# 3tastsp_v4_resistorcooldrive_battcheck.net
KiCad netlist of a schematic drawn in EAGLE
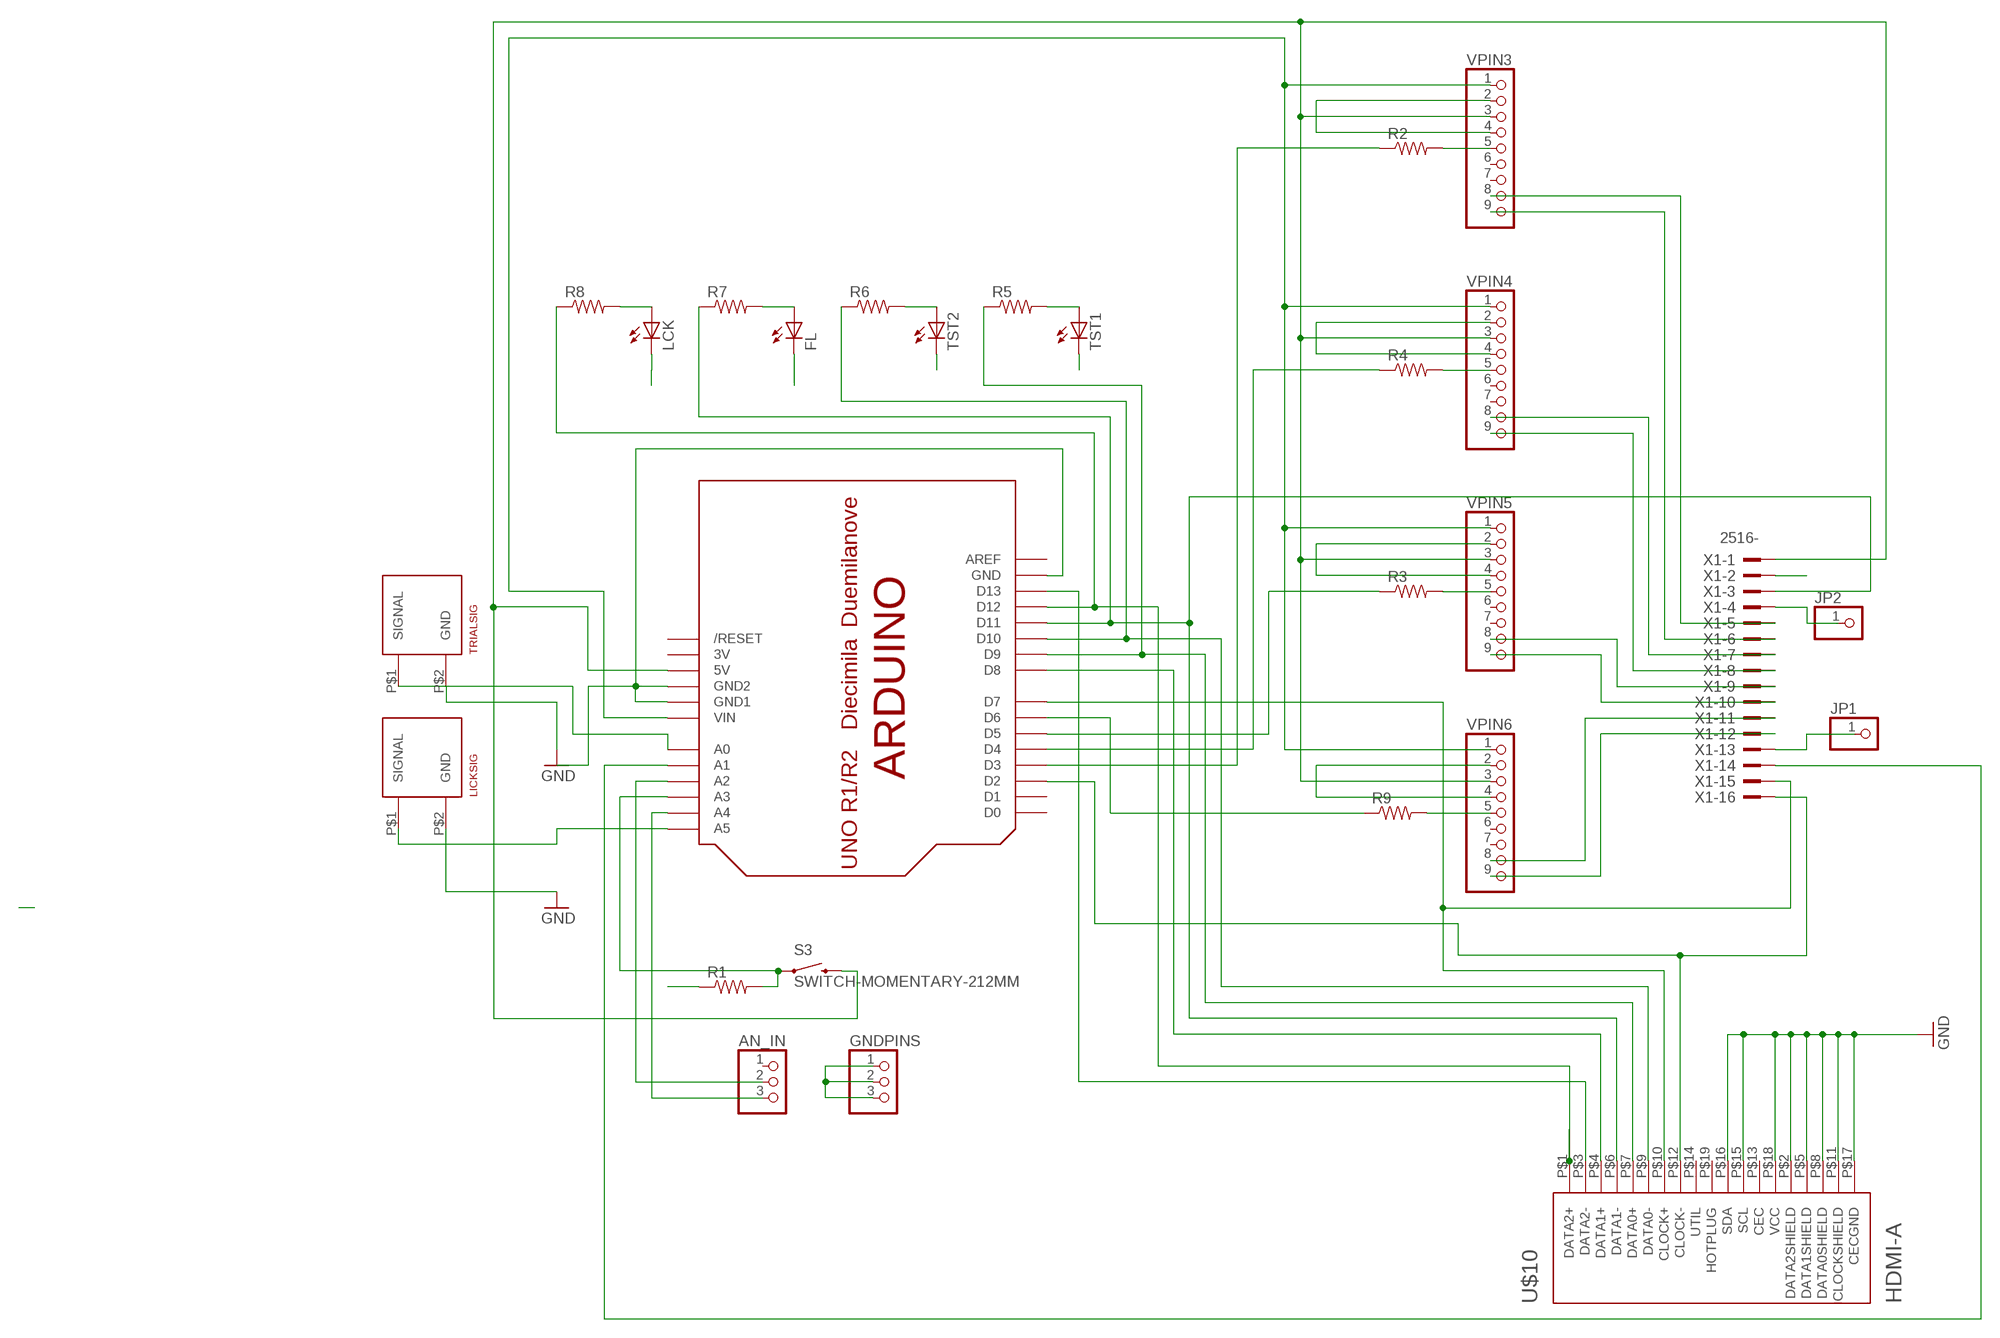
[diagram p0: schematic, sheet 1]

(export (version "E")
  (design (tool "Eeschema 10.0.6"))
  (components
    (comp (ref "AN_IN")
      (value "PINHD-1X3")
      (footprint "eagle-import:1X03")
      (libsource (lib "eagle-import") (part "PINHD-1X3"))
    )
    (comp (ref "FL")
      (value "LED5MM")
      (footprint "eagle-import:LED5MM")
      (libsource (lib "eagle-import") (part "LED5MM"))
    )
    (comp (ref "GNDPINS")
      (value "PINHD-1X3")
      (footprint "eagle-import:1X03")
      (libsource (lib "eagle-import") (part "PINHD-1X3"))
    )
    (comp (ref "JP1")
      (value "PINHD-1X1")
      (footprint "eagle-import:1X01")
      (libsource (lib "eagle-import") (part "PINHD-1X1"))
    )
    (comp (ref "JP2")
      (value "PINHD-1X1")
      (footprint "eagle-import:1X01")
      (libsource (lib "eagle-import") (part "PINHD-1X1"))
    )
    (comp (ref "LCK")
      (value "LED5MM")
      (footprint "eagle-import:LED5MM")
      (libsource (lib "eagle-import") (part "LED5MM"))
    )
    (comp (ref "LICKSIG")
      (value "BNC_VERTICAL")
      (footprint "eagle-import:BNC_VERTICAL")
      (libsource (lib "eagle-import") (part "BNC_VERTICAL"))
    )
    (comp (ref "R1")
      (value "RESISTORPTH-1/2W")
      (footprint "eagle-import:AXIAL-0.5")
      (libsource (lib "eagle-import") (part "RESISTORPTH-1/2W"))
    )
    (comp (ref "R2")
      (value "RESISTORPTH-1/2W")
      (footprint "eagle-import:AXIAL-0.5")
      (libsource (lib "eagle-import") (part "RESISTORPTH-1/2W"))
    )
    (comp (ref "R3")
      (value "RESISTORPTH-1/2W")
      (footprint "eagle-import:AXIAL-0.5")
      (libsource (lib "eagle-import") (part "RESISTORPTH-1/2W"))
    )
    (comp (ref "R4")
      (value "RESISTORPTH-1/2W")
      (footprint "eagle-import:AXIAL-0.5")
      (libsource (lib "eagle-import") (part "RESISTORPTH-1/2W"))
    )
    (comp (ref "R5")
      (value "RESISTORPTH-1/2W")
      (footprint "eagle-import:AXIAL-0.5")
      (libsource (lib "eagle-import") (part "RESISTORPTH-1/2W"))
    )
    (comp (ref "R6")
      (value "RESISTORPTH-1/2W")
      (footprint "eagle-import:AXIAL-0.5")
      (libsource (lib "eagle-import") (part "RESISTORPTH-1/2W"))
    )
    (comp (ref "R7")
      (value "RESISTORPTH-1/2W")
      (footprint "eagle-import:AXIAL-0.5")
      (libsource (lib "eagle-import") (part "RESISTORPTH-1/2W"))
    )
    (comp (ref "R8")
      (value "RESISTORPTH-1/2W")
      (footprint "eagle-import:AXIAL-0.5")
      (libsource (lib "eagle-import") (part "RESISTORPTH-1/2W"))
    )
    (comp (ref "R9")
      (value "RESISTORPTH-1/2W")
      (footprint "eagle-import:AXIAL-0.5")
      (libsource (lib "eagle-import") (part "RESISTORPTH-1/2W"))
    )
    (comp (ref "S3")
      (value "SWITCH-MOMENTARY-212MM")
      (footprint "eagle-import:TACTILE-PTH-12MM")
      (libsource (lib "eagle-import") (part "SWITCH-MOMENTARY-212MM"))
    )
    (comp (ref "TRIALSIG")
      (value "BNC_VERTICAL")
      (footprint "eagle-import:BNC_VERTICAL")
      (libsource (lib "eagle-import") (part "BNC_VERTICAL"))
    )
    (comp (ref "TST1")
      (value "LED5MM")
      (footprint "eagle-import:LED5MM")
      (libsource (lib "eagle-import") (part "LED5MM"))
    )
    (comp (ref "TST2")
      (value "LED5MM")
      (footprint "eagle-import:LED5MM")
      (libsource (lib "eagle-import") (part "LED5MM"))
    )
    (comp (ref "U$1")
      (value "ARDUINO-NOHOLE")
      (footprint "eagle-import:ARDUINO-NOHOLE")
      (libsource (lib "eagle-import") (part "ARDUINO-NOHOLE"))
    )
    (comp (ref "U$10")
      (value "HDMI-A")
      (footprint "eagle-import:HDMI_A")
      (libsource (lib "eagle-import") (part "HDMI-A"))
    )
    (comp (ref "VPIN3")
      (value "PINHD-1X9")
      (footprint "eagle-import:1X09")
      (libsource (lib "eagle-import") (part "PINHD-1X9"))
    )
    (comp (ref "VPIN4")
      (value "PINHD-1X9")
      (footprint "eagle-import:1X09")
      (libsource (lib "eagle-import") (part "PINHD-1X9"))
    )
    (comp (ref "VPIN5")
      (value "PINHD-1X9")
      (footprint "eagle-import:1X09")
      (libsource (lib "eagle-import") (part "PINHD-1X9"))
    )
    (comp (ref "VPIN6")
      (value "PINHD-1X9")
      (footprint "eagle-import:1X09")
      (libsource (lib "eagle-import") (part "PINHD-1X9"))
    )
    (comp (ref "X1")
      (value "2516-")
      (footprint "eagle-import:PAK100_2500-16")
      (libsource (lib "eagle-import") (part "2516-"))
    )
  )
  (nets
    (net (code "1") (name "/3V") (class "Default")
      (node (ref "U$1") (pin "3V") (pinfunction "3V_3V") (pintype "power_in"))
    )
    (net (code "2") (name "GND") (class "Default")
      (node (ref "FL") (pin "K") (pinfunction "C_K") (pintype "passive"))
      (node (ref "GNDPINS") (pin "1") (pinfunction "1_1") (pintype "passive"))
      (node (ref "GNDPINS") (pin "2") (pinfunction "2_2") (pintype "passive"))
      (node (ref "GNDPINS") (pin "3") (pinfunction "3_3") (pintype "passive"))
      (node (ref "LCK") (pin "K") (pinfunction "C_K") (pintype "passive"))
      (node (ref "LICKSIG") (pin "P$2") (pinfunction "GND_P$2") (pintype "bidirectional"))
      (node (ref "R1") (pin "P$1") (pinfunction "1_P$1") (pintype "passive"))
      (node (ref "TRIALSIG") (pin "P$2") (pinfunction "GND_P$2") (pintype "bidirectional"))
      (node (ref "TST1") (pin "K") (pinfunction "C_K") (pintype "passive"))
      (node (ref "TST2") (pin "K") (pinfunction "C_K") (pintype "passive"))
      (node (ref "U$1") (pin "GND") (pinfunction "GND_GND") (pintype "power_in"))
      (node (ref "U$1") (pin "GND1") (pinfunction "GND1_GND1") (pintype "power_in"))
      (node (ref "U$1") (pin "GND2") (pinfunction "GND2_GND2") (pintype "power_in"))
      (node (ref "U$10") (pin "P$11") (pinfunction "CLOCKSHIELD_P$11") (pintype "bidirectional"))
      (node (ref "U$10") (pin "P$15") (pinfunction "SCL_P$15") (pintype "bidirectional"))
      (node (ref "U$10") (pin "P$16") (pinfunction "SDA_P$16") (pintype "bidirectional"))
      (node (ref "U$10") (pin "P$17") (pinfunction "CECGND_P$17") (pintype "bidirectional"))
      (node (ref "U$10") (pin "P$18") (pinfunction "VCC_P$18") (pintype "bidirectional"))
      (node (ref "U$10") (pin "P$2") (pinfunction "DATA2SHIELD_P$2") (pintype "bidirectional"))
      (node (ref "U$10") (pin "P$5") (pinfunction "DATA1SHIELD_P$5") (pintype "bidirectional"))
      (node (ref "U$10") (pin "P$8") (pinfunction "DATA0SHIELD_P$8") (pintype "bidirectional"))
      (node (ref "VPIN3") (pin "2") (pinfunction "2_2") (pintype "passive"))
      (node (ref "VPIN3") (pin "4") (pinfunction "4_4") (pintype "passive"))
      (node (ref "VPIN4") (pin "2") (pinfunction "2_2") (pintype "passive"))
      (node (ref "VPIN4") (pin "4") (pinfunction "4_4") (pintype "passive"))
      (node (ref "VPIN5") (pin "2") (pinfunction "2_2") (pintype "passive"))
      (node (ref "VPIN5") (pin "4") (pinfunction "4_4") (pintype "passive"))
      (node (ref "VPIN6") (pin "2") (pinfunction "2_2") (pintype "passive"))
      (node (ref "VPIN6") (pin "4") (pinfunction "4_4") (pintype "passive"))
      (node (ref "X1") (pin "2") (pinfunction "KL_2") (pintype "passive"))
    )
    (net (code "3") (name "Net-(AN_IN-Pad2)") (class "Default")
      (node (ref "AN_IN") (pin "2") (pinfunction "2_2") (pintype "passive"))
      (node (ref "U$1") (pin "A2") (pinfunction "A2_A2") (pintype "bidirectional"))
    )
    (net (code "4") (name "Net-(AN_IN-Pad3)") (class "Default")
      (node (ref "AN_IN") (pin "3") (pinfunction "3_3") (pintype "passive"))
      (node (ref "U$1") (pin "A4") (pinfunction "A4_A4") (pintype "bidirectional"))
    )
    (net (code "5") (name "Net-(LICKSIG-SIGNAL)") (class "Default")
      (node (ref "LICKSIG") (pin "P$1") (pinfunction "SIGNAL_P$1") (pintype "bidirectional"))
      (node (ref "U$1") (pin "A5") (pinfunction "A5_A5") (pintype "bidirectional"))
    )
    (net (code "6") (name "Net-(R1-2)") (class "Default")
      (node (ref "R1") (pin "P$2") (pinfunction "2_P$2") (pintype "passive"))
      (node (ref "S3") (pin "1") (pinfunction "1_1") (pintype "passive"))
      (node (ref "U$1") (pin "A3") (pinfunction "A3_A3") (pintype "bidirectional"))
    )
    (net (code "7") (name "Net-(R2-1)") (class "Default")
      (node (ref "R2") (pin "P$1") (pinfunction "1_P$1") (pintype "passive"))
      (node (ref "U$1") (pin "D3") (pinfunction "D3_D3") (pintype "bidirectional"))
    )
    (net (code "8") (name "Net-(R2-2)") (class "Default")
      (node (ref "R2") (pin "P$2") (pinfunction "2_P$2") (pintype "passive"))
      (node (ref "VPIN3") (pin "5") (pinfunction "5_5") (pintype "passive"))
    )
    (net (code "9") (name "Net-(R3-1)") (class "Default")
      (node (ref "R3") (pin "P$1") (pinfunction "1_P$1") (pintype "passive"))
      (node (ref "U$1") (pin "D5") (pinfunction "D5_D5") (pintype "bidirectional"))
    )
    (net (code "10") (name "Net-(R3-2)") (class "Default")
      (node (ref "R3") (pin "P$2") (pinfunction "2_P$2") (pintype "passive"))
      (node (ref "VPIN5") (pin "5") (pinfunction "5_5") (pintype "passive"))
    )
    (net (code "11") (name "Net-(R4-1)") (class "Default")
      (node (ref "R4") (pin "P$1") (pinfunction "1_P$1") (pintype "passive"))
      (node (ref "U$1") (pin "D4") (pinfunction "D4_D4") (pintype "bidirectional"))
    )
    (net (code "12") (name "Net-(R4-2)") (class "Default")
      (node (ref "R4") (pin "P$2") (pinfunction "2_P$2") (pintype "passive"))
      (node (ref "VPIN4") (pin "5") (pinfunction "5_5") (pintype "passive"))
    )
    (net (code "13") (name "Net-(R5-1)") (class "Default")
      (node (ref "R5") (pin "P$1") (pinfunction "1_P$1") (pintype "passive"))
      (node (ref "U$1") (pin "D9") (pinfunction "D9_D9") (pintype "bidirectional"))
      (node (ref "U$10") (pin "P$7") (pinfunction "DATA0+_P$7") (pintype "bidirectional"))
    )
    (net (code "14") (name "Net-(R5-2)") (class "Default")
      (node (ref "R5") (pin "P$2") (pinfunction "2_P$2") (pintype "passive"))
      (node (ref "TST1") (pin "A") (pinfunction "A_A") (pintype "passive"))
    )
    (net (code "15") (name "Net-(R6-1)") (class "Default")
      (node (ref "R6") (pin "P$1") (pinfunction "1_P$1") (pintype "passive"))
      (node (ref "U$1") (pin "D10") (pinfunction "D10_D10") (pintype "bidirectional"))
      (node (ref "U$10") (pin "P$9") (pinfunction "DATA0-_P$9") (pintype "bidirectional"))
    )
    (net (code "16") (name "Net-(R6-2)") (class "Default")
      (node (ref "R6") (pin "P$2") (pinfunction "2_P$2") (pintype "passive"))
      (node (ref "TST2") (pin "A") (pinfunction "A_A") (pintype "passive"))
    )
    (net (code "17") (name "Net-(R7-1)") (class "Default")
      (node (ref "R7") (pin "P$1") (pinfunction "1_P$1") (pintype "passive"))
      (node (ref "U$1") (pin "D11") (pinfunction "D11_D11") (pintype "bidirectional"))
      (node (ref "U$10") (pin "P$6") (pinfunction "DATA1-_P$6") (pintype "bidirectional"))
      (node (ref "X1") (pin "3") (pinfunction "KL_3") (pintype "passive"))
    )
    (net (code "18") (name "Net-(R7-2)") (class "Default")
      (node (ref "FL") (pin "A") (pinfunction "A_A") (pintype "passive"))
      (node (ref "R7") (pin "P$2") (pinfunction "2_P$2") (pintype "passive"))
    )
    (net (code "19") (name "Net-(R8-1)") (class "Default")
      (node (ref "R8") (pin "P$1") (pinfunction "1_P$1") (pintype "passive"))
      (node (ref "U$1") (pin "D12") (pinfunction "D12_D12") (pintype "bidirectional"))
      (node (ref "U$10") (pin "P$1") (pinfunction "DATA2+_P$1") (pintype "bidirectional"))
    )
    (net (code "20") (name "Net-(R8-2)") (class "Default")
      (node (ref "LCK") (pin "A") (pinfunction "A_A") (pintype "passive"))
      (node (ref "R8") (pin "P$2") (pinfunction "2_P$2") (pintype "passive"))
    )
    (net (code "21") (name "Net-(R9-1)") (class "Default")
      (node (ref "R9") (pin "P$1") (pinfunction "1_P$1") (pintype "passive"))
      (node (ref "U$1") (pin "D6") (pinfunction "D6_D6") (pintype "bidirectional"))
    )
    (net (code "22") (name "Net-(R9-2)") (class "Default")
      (node (ref "R9") (pin "P$2") (pinfunction "2_P$2") (pintype "passive"))
      (node (ref "VPIN6") (pin "5") (pinfunction "5_5") (pintype "passive"))
    )
    (net (code "23") (name "Net-(S3-2)") (class "Default")
      (node (ref "S3") (pin "3") (pinfunction "2_3") (pintype "passive"))
      (node (ref "U$1") (pin "5V") (pinfunction "5V_5V") (pintype "power_in"))
      (node (ref "VPIN3") (pin "3") (pinfunction "3_3") (pintype "passive"))
      (node (ref "VPIN4") (pin "3") (pinfunction "3_3") (pintype "passive"))
      (node (ref "VPIN5") (pin "3") (pinfunction "3_3") (pintype "passive"))
      (node (ref "VPIN6") (pin "3") (pinfunction "3_3") (pintype "passive"))
      (node (ref "X1") (pin "1") (pinfunction "KL_1") (pintype "passive"))
    )
    (net (code "24") (name "Net-(TRIALSIG-SIGNAL)") (class "Default")
      (node (ref "TRIALSIG") (pin "P$1") (pinfunction "SIGNAL_P$1") (pintype "bidirectional"))
      (node (ref "U$1") (pin "A0") (pinfunction "A0_A0") (pintype "bidirectional"))
    )
    (net (code "25") (name "Net-(U$1-PadVIN)") (class "Default")
      (node (ref "U$1") (pin "VIN") (pinfunction "VIN_VIN") (pintype "power_in"))
      (node (ref "VPIN3") (pin "1") (pinfunction "1_1") (pintype "passive"))
      (node (ref "VPIN4") (pin "1") (pinfunction "1_1") (pintype "passive"))
      (node (ref "VPIN5") (pin "1") (pinfunction "1_1") (pintype "passive"))
      (node (ref "VPIN6") (pin "1") (pinfunction "1_1") (pintype "passive"))
    )
    (net (code "26") (name "Net-(U$10-CLOCK+)") (class "Default")
      (node (ref "U$1") (pin "D7") (pinfunction "D7_D7") (pintype "bidirectional"))
      (node (ref "U$10") (pin "P$10") (pinfunction "CLOCK+_P$10") (pintype "bidirectional"))
      (node (ref "X1") (pin "15") (pinfunction "KL_15") (pintype "passive"))
    )
    (net (code "27") (name "Net-(U$10-CLOCK-)") (class "Default")
      (node (ref "U$1") (pin "D2") (pinfunction "D2_D2") (pintype "bidirectional"))
      (node (ref "U$10") (pin "P$12") (pinfunction "CLOCK-_P$12") (pintype "bidirectional"))
      (node (ref "X1") (pin "16") (pinfunction "KL_16") (pintype "passive"))
    )
    (net (code "28") (name "Net-(U$10-DATA1+)") (class "Default")
      (node (ref "U$1") (pin "D8") (pinfunction "D8_D8") (pintype "bidirectional"))
      (node (ref "U$10") (pin "P$4") (pinfunction "DATA1+_P$4") (pintype "bidirectional"))
    )
    (net (code "29") (name "Net-(U$10-DATA2-)") (class "Default")
      (node (ref "U$1") (pin "D13") (pinfunction "D13_D13") (pintype "bidirectional"))
      (node (ref "U$10") (pin "P$3") (pinfunction "DATA2-_P$3") (pintype "bidirectional"))
    )
    (net (code "30") (name "Net-(X1B-KL)") (class "Default")
      (node (ref "VPIN5") (pin "9") (pinfunction "9_9") (pintype "passive"))
      (node (ref "X1") (pin "10") (pinfunction "KL_10") (pintype "passive"))
    )
    (net (code "31") (name "Net-(X1C-KL)") (class "Default")
      (node (ref "VPIN6") (pin "8") (pinfunction "8_8") (pintype "passive"))
      (node (ref "X1") (pin "11") (pinfunction "KL_11") (pintype "passive"))
    )
    (net (code "32") (name "Net-(X1D-KL)") (class "Default")
      (node (ref "VPIN6") (pin "9") (pinfunction "9_9") (pintype "passive"))
      (node (ref "X1") (pin "12") (pinfunction "KL_12") (pintype "passive"))
    )
    (net (code "33") (name "Net-(X1E-KL)") (class "Default")
      (node (ref "JP1") (pin "1") (pinfunction "1_1") (pintype "passive"))
      (node (ref "X1") (pin "13") (pinfunction "KL_13") (pintype "passive"))
    )
    (net (code "34") (name "Net-(X1F-KL)") (class "Default")
      (node (ref "U$1") (pin "A1") (pinfunction "A1_A1") (pintype "bidirectional"))
      (node (ref "X1") (pin "14") (pinfunction "KL_14") (pintype "passive"))
    )
    (net (code "35") (name "Net-(X1K-KL)") (class "Default")
      (node (ref "JP2") (pin "1") (pinfunction "1_1") (pintype "passive"))
      (node (ref "X1") (pin "4") (pinfunction "KL_4") (pintype "passive"))
    )
    (net (code "36") (name "Net-(X1L-KL)") (class "Default")
      (node (ref "VPIN3") (pin "8") (pinfunction "8_8") (pintype "passive"))
      (node (ref "X1") (pin "5") (pinfunction "KL_5") (pintype "passive"))
    )
    (net (code "37") (name "Net-(X1M-KL)") (class "Default")
      (node (ref "VPIN3") (pin "9") (pinfunction "9_9") (pintype "passive"))
      (node (ref "X1") (pin "6") (pinfunction "KL_6") (pintype "passive"))
    )
    (net (code "38") (name "Net-(X1N-KL)") (class "Default")
      (node (ref "VPIN4") (pin "8") (pinfunction "8_8") (pintype "passive"))
      (node (ref "X1") (pin "7") (pinfunction "KL_7") (pintype "passive"))
    )
    (net (code "39") (name "Net-(X1O-KL)") (class "Default")
      (node (ref "VPIN4") (pin "9") (pinfunction "9_9") (pintype "passive"))
      (node (ref "X1") (pin "8") (pinfunction "KL_8") (pintype "passive"))
    )
    (net (code "40") (name "Net-(X1P-KL)") (class "Default")
      (node (ref "VPIN5") (pin "8") (pinfunction "8_8") (pintype "passive"))
      (node (ref "X1") (pin "9") (pinfunction "KL_9") (pintype "passive"))
    )
    (net (code "41") (name "unconnected-(AN_IN-Pad1)") (class "Default")
      (node (ref "AN_IN") (pin "1") (pinfunction "1_1") (pintype "passive"))
    )
    (net (code "42") (name "unconnected-(U$1-PadAREF)") (class "Default")
      (node (ref "U$1") (pin "AREF") (pinfunction "AREF_AREF") (pintype "bidirectional"))
    )
    (net (code "43") (name "unconnected-(U$1-PadD0)") (class "Default")
      (node (ref "U$1") (pin "D0") (pinfunction "D0_D0") (pintype "bidirectional"))
    )
    (net (code "44") (name "unconnected-(U$1-PadD1)") (class "Default")
      (node (ref "U$1") (pin "D1") (pinfunction "D1_D1") (pintype "bidirectional"))
    )
    (net (code "45") (name "unconnected-(U$1-{slash}RESET-PadRESET)") (class "Default")
      (node (ref "U$1") (pin "RESET") (pinfunction "/RESET_RESET") (pintype "bidirectional"))
    )
    (net (code "46") (name "unconnected-(U$10-CEC-PadP$13)") (class "Default")
      (node (ref "U$10") (pin "P$13") (pinfunction "CEC_P$13") (pintype "bidirectional"))
    )
    (net (code "47") (name "unconnected-(U$10-HOTPLUG-PadP$19)") (class "Default")
      (node (ref "U$10") (pin "P$19") (pinfunction "HOTPLUG_P$19") (pintype "bidirectional"))
    )
    (net (code "48") (name "unconnected-(U$10-UTIL-PadP$14)") (class "Default")
      (node (ref "U$10") (pin "P$14") (pinfunction "UTIL_P$14") (pintype "bidirectional"))
    )
    (net (code "49") (name "unconnected-(VPIN3-Pad6)") (class "Default")
      (node (ref "VPIN3") (pin "6") (pinfunction "6_6") (pintype "passive"))
    )
    (net (code "50") (name "unconnected-(VPIN3-Pad7)") (class "Default")
      (node (ref "VPIN3") (pin "7") (pinfunction "7_7") (pintype "passive"))
    )
    (net (code "51") (name "unconnected-(VPIN4-Pad6)") (class "Default")
      (node (ref "VPIN4") (pin "6") (pinfunction "6_6") (pintype "passive"))
    )
    (net (code "52") (name "unconnected-(VPIN4-Pad7)") (class "Default")
      (node (ref "VPIN4") (pin "7") (pinfunction "7_7") (pintype "passive"))
    )
    (net (code "53") (name "unconnected-(VPIN5-Pad6)") (class "Default")
      (node (ref "VPIN5") (pin "6") (pinfunction "6_6") (pintype "passive"))
    )
    (net (code "54") (name "unconnected-(VPIN5-Pad7)") (class "Default")
      (node (ref "VPIN5") (pin "7") (pinfunction "7_7") (pintype "passive"))
    )
    (net (code "55") (name "unconnected-(VPIN6-Pad6)") (class "Default")
      (node (ref "VPIN6") (pin "6") (pinfunction "6_6") (pintype "passive"))
    )
    (net (code "56") (name "unconnected-(VPIN6-Pad7)") (class "Default")
      (node (ref "VPIN6") (pin "7") (pinfunction "7_7") (pintype "passive"))
    )
  )
)
